# Sheet_1.net
KiCad netlist of a schematic drawn in Altium Designer
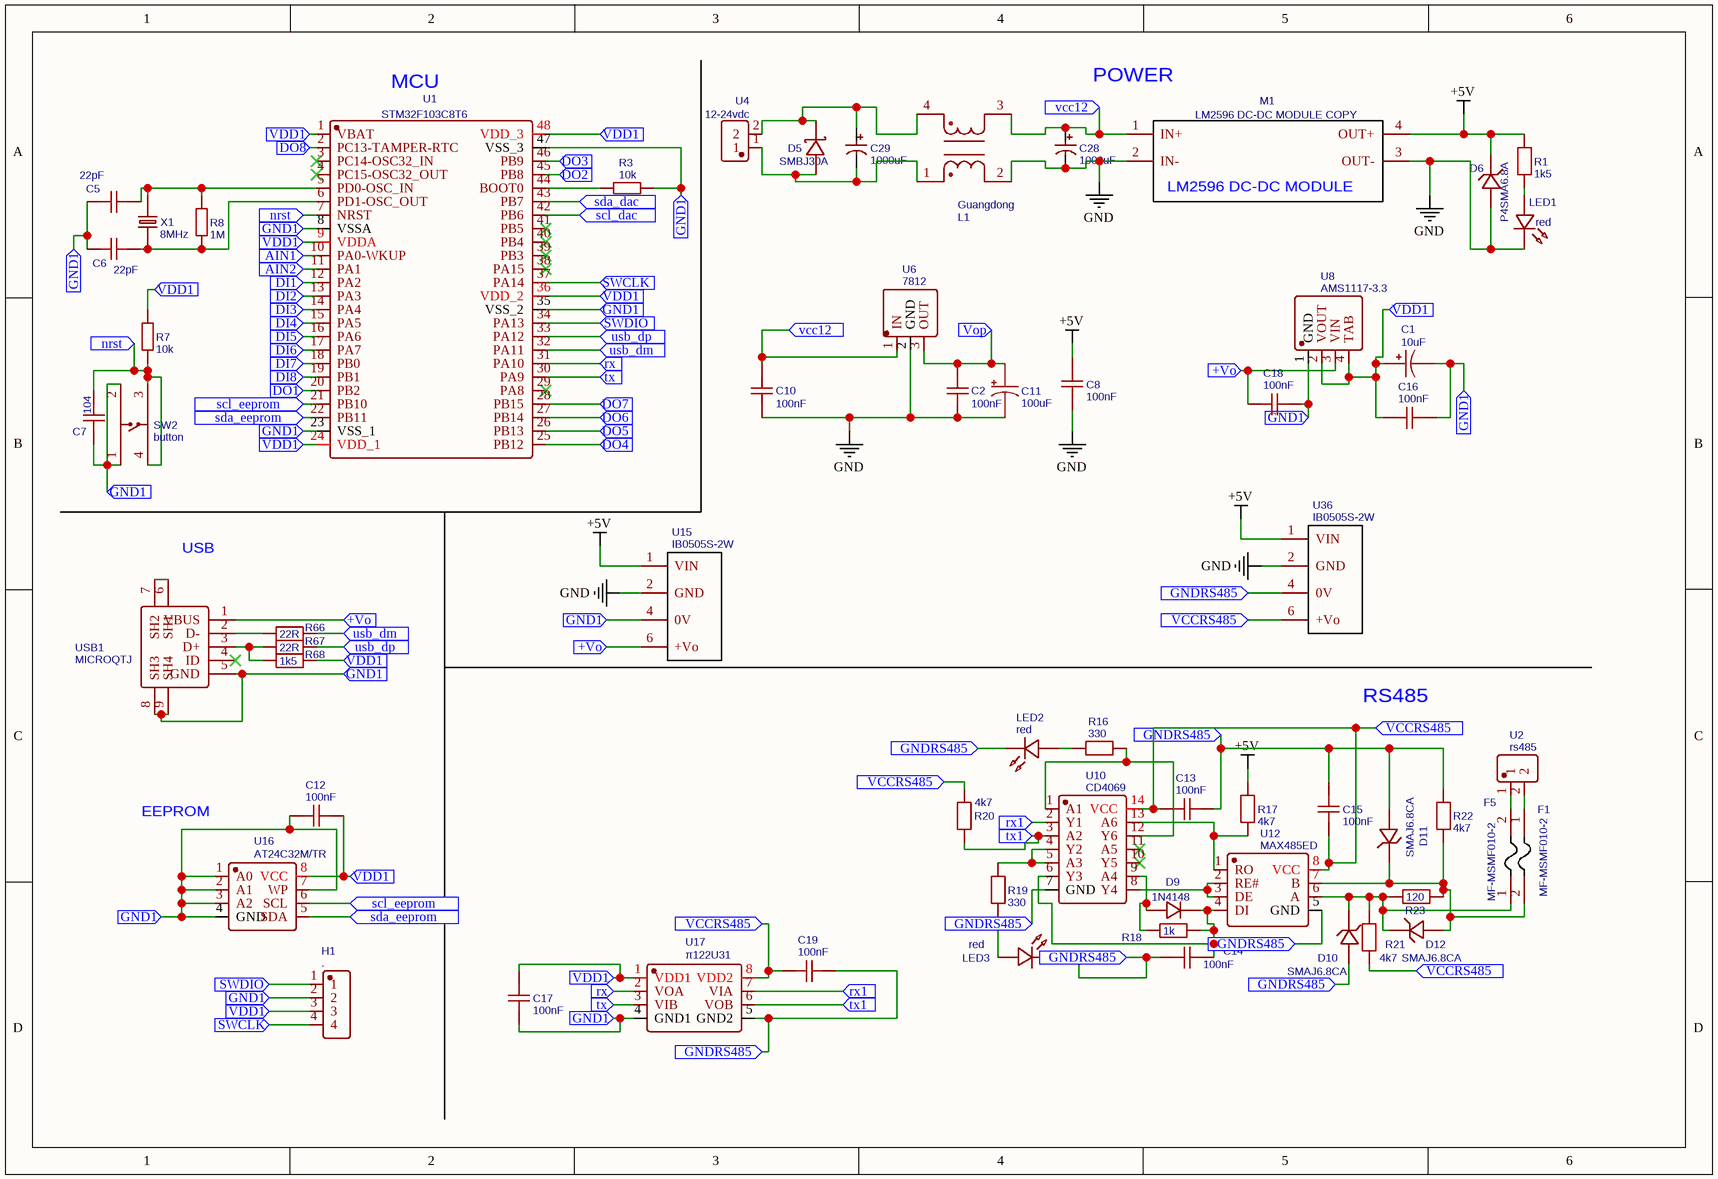
[diagram p0: Sheet_1.schdoc]

(export (version "E")
  (design (tool "Eeschema 10.0.6"))
  (components
    (comp (ref "C1")
      (value "10uF")
      (fields
        (field (name "BOM_SUPPLIER PART") "C503219")
        (field (name "BOM_MANUFACTURER PART") "01EC1809SHC10UF50V")
        (field (name "CONTRIBUTOR") "LCSC")
      )
      (libsource (lib "altium-import") (part "root_0_10uF_"))
    )
    (comp (ref "C2")
      (value "100nF")
      (fields
        (field (name "BOM_SUPPLIER PART") "C254075")
        (field (name "BOM_MANUFACTURER PART") "CC1H333ZA1PD3F4D30MF")
        (field (name "CONTRIBUTOR") "LCSC")
      )
      (libsource (lib "altium-import") (part "root_0_100nF_"))
    )
    (comp (ref "C5")
      (value "22pF")
      (fields
        (field (name "BOM_SUPPLIER PART") "C277970")
        (field (name "BOM_MANUFACTURER PART") "CC1-F5U2J2B330KSPW")
        (field (name "CONTRIBUTOR") "LCSC")
      )
      (libsource (lib "altium-import") (part "root_0_22pF_"))
    )
    (comp (ref "C6")
      (value "22pF")
      (fields
        (field (name "BOM_SUPPLIER PART") "C277970")
        (field (name "BOM_MANUFACTURER PART") "CC1-F5U2J2B330KSPW")
        (field (name "CONTRIBUTOR") "LCSC")
      )
      (libsource (lib "altium-import") (part "root_0_22pF_"))
    )
    (comp (ref "C7")
      (value "104")
      (fields
        (field (name "BOM_SUPPLIER PART") "C277970")
        (field (name "BOM_MANUFACTURER PART") "CC1-F5U2J2B330KSPW")
        (field (name "CONTRIBUTOR") "LCSC")
      )
      (libsource (lib "altium-import") (part "root_1_104_"))
    )
    (comp (ref "C8")
      (value "100nF")
      (fields
        (field (name "BOM_SUPPLIER PART") "C254075")
        (field (name "BOM_MANUFACTURER PART") "CC1H333ZA1PD3F4D30MF")
        (field (name "CONTRIBUTOR") "LCSC")
      )
      (libsource (lib "altium-import") (part "root_2_100nF_"))
    )
    (comp (ref "C10")
      (value "100nF")
      (fields
        (field (name "BOM_SUPPLIER PART") "C254075")
        (field (name "BOM_MANUFACTURER PART") "CC1H333ZA1PD3F4D30MF")
        (field (name "CONTRIBUTOR") "LCSC")
      )
      (libsource (lib "altium-import") (part "root_0_100nF_"))
    )
    (comp (ref "C11")
      (value "100uF")
      (fields
        (field (name "BOM_SUPPLIER PART") "C503221")
        (field (name "BOM_MANUFACTURER PART") "01EC1227SHC470UF25V")
        (field (name "CONTRIBUTOR") "LCSC")
      )
      (libsource (lib "altium-import") (part "root_0_100uF_"))
    )
    (comp (ref "C12")
      (value "100nF")
      (fields
        (field (name "BOM_SUPPLIER PART") "C254075")
        (field (name "BOM_MANUFACTURER PART") "CC1H333ZA1PD3F4D30MF")
        (field (name "CONTRIBUTOR") "LCSC")
      )
      (libsource (lib "altium-import") (part "root_1_100nF_"))
    )
    (comp (ref "C13")
      (value "100nF")
      (fields
        (field (name "BOM_SUPPLIER PART") "C254075")
        (field (name "BOM_MANUFACTURER PART") "CC1H333ZA1PD3F4D30MF")
        (field (name "CONTRIBUTOR") "LCSC")
      )
      (libsource (lib "altium-import") (part "root_1_100nF_"))
    )
    (comp (ref "C14")
      (value "100nF")
      (fields
        (field (name "BOM_SUPPLIER PART") "C254075")
        (field (name "BOM_MANUFACTURER PART") "CC1H333ZA1PD3F4D30MF")
        (field (name "CONTRIBUTOR") "LCSC")
      )
      (libsource (lib "altium-import") (part "root_3_100nF_"))
    )
    (comp (ref "C15")
      (value "100nF")
      (fields
        (field (name "BOM_SUPPLIER PART") "C254075")
        (field (name "BOM_MANUFACTURER PART") "CC1H333ZA1PD3F4D30MF")
        (field (name "CONTRIBUTOR") "LCSC")
      )
      (libsource (lib "altium-import") (part "root_2_100nF_"))
    )
    (comp (ref "C16")
      (value "100nF")
      (fields
        (field (name "BOM_SUPPLIER PART") "C254075")
        (field (name "BOM_MANUFACTURER PART") "CC1H333ZA1PD3F4D30MF")
        (field (name "CONTRIBUTOR") "LCSC")
      )
      (libsource (lib "altium-import") (part "root_1_100nF_"))
    )
    (comp (ref "C17")
      (value "100nF")
      (fields
        (field (name "BOM_SUPPLIER PART") "C254075")
        (field (name "BOM_MANUFACTURER PART") "CC1H333ZA1PD3F4D30MF")
        (field (name "CONTRIBUTOR") "LCSC")
      )
      (libsource (lib "altium-import") (part "root_2_100nF_"))
    )
    (comp (ref "C18")
      (value "100nF")
      (fields
        (field (name "BOM_SUPPLIER PART") "C254075")
        (field (name "BOM_MANUFACTURER PART") "CC1H333ZA1PD3F4D30MF")
        (field (name "CONTRIBUTOR") "LCSC")
      )
      (libsource (lib "altium-import") (part "root_1_100nF_"))
    )
    (comp (ref "C19")
      (value "100nF")
      (fields
        (field (name "BOM_SUPPLIER PART") "C254075")
        (field (name "BOM_MANUFACTURER PART") "CC1H333ZA1PD3F4D30MF")
        (field (name "CONTRIBUTOR") "LCSC")
      )
      (libsource (lib "altium-import") (part "root_1_100nF_"))
    )
    (comp (ref "C28")
      (value "1000uF")
      (fields
        (field (name "BOM_MANUFACTURER PART") "1000uF 35V 13*20")
        (field (name "BOM_SUPPLIER PART") "C10749")
      )
      (libsource (lib "altium-import") (part "root_3_1000uF_"))
    )
    (comp (ref "C29")
      (value "1000uF")
      (fields
        (field (name "BOM_MANUFACTURER PART") "1000uF 35V 13*20")
        (field (name "BOM_SUPPLIER PART") "C10749")
      )
      (libsource (lib "altium-import") (part "root_3_1000uF_"))
    )
    (comp (ref "D5")
      (value "SMBJ30A")
      (fields (field (name "BOM_SUPPLIER PART") "C305669") (field (name "CONTRIBUTOR") "LCSC"))
      (libsource (lib "altium-import") (part "root_3_SMBJ30A_"))
    )
    (comp (ref "D6")
      (value "P4SMA6.8A")
      (fields (field (name "BOM_SUPPLIER PART") "C2758558") (field (name "CONTRIBUTOR") "LCSC"))
      (libsource (lib "altium-import") (part "root_3_P4SMA6.8A_"))
    )
    (comp (ref "D9")
      (value "1N4148")
      (fields (field (name "BOM_SUPPLIER PART") "C85057"))
      (libsource (lib "altium-import") (part "root_2_1N4148_"))
    )
    (comp (ref "D10")
      (value "SMAJ6.8CA")
      (fields
        (field (name "BOM_SUPPLIER PART") "C521797")
        (field (name "BOM_MANUFACTURER PART") "1.5KE12A")
        (field (name "CONTRIBUTOR") "LCSC")
      )
      (libsource (lib "altium-import") (part "root_3_SMAJ6.8CA_"))
    )
    (comp (ref "D11")
      (value "SMAJ6.8CA")
      (fields
        (field (name "BOM_SUPPLIER PART") "C521797")
        (field (name "BOM_MANUFACTURER PART") "1.5KE12A")
        (field (name "CONTRIBUTOR") "LCSC")
      )
      (libsource (lib "altium-import") (part "root_1_SMAJ6.8CA_"))
    )
    (comp (ref "D12")
      (value "SMAJ6.8CA")
      (fields
        (field (name "BOM_SUPPLIER PART") "C521797")
        (field (name "BOM_MANUFACTURER PART") "1.5KE12A")
        (field (name "CONTRIBUTOR") "LCSC")
      )
      (libsource (lib "altium-import") (part "root_0_SMAJ6.8CA_"))
    )
    (comp (ref "F1")
      (value "MF-MSMF010-2")
      (fields (field (name "BOM_SUPPLIER PART") "C12430"))
      (libsource (lib "altium-import") (part "root_3_MF-MSMF010-2_"))
    )
    (comp (ref "F5")
      (value "MF-MSMF010-2")
      (fields (field (name "BOM_SUPPLIER PART") "C12430"))
      (libsource (lib "altium-import") (part "root_1_MF-MSMF010-2_"))
    )
    (comp (ref "H1")
      (value ".")
      (fields
        (field (name "BOM_SUPPLIER PART") "C355292")
        (field (name "BOM_MANUFACTURER PART") "12251104CNSNS295001")
        (field (name "CONTRIBUTOR") "LCSC")
      )
      (libsource (lib "altium-import") (part "root_0_._"))
    )
    (comp (ref "L1")
      (value "Guangdong")
      (fields
        (field (name "BOM_SUPPLIER PART") "C116373")
        (field (name "BOM_MANUFACTURER PART") "UU9.8-5mH")
        (field (name "CONTRIBUTOR") "LCSC")
      )
      (libsource (lib "altium-import") (part "root_0_Guangdong_"))
    )
    (comp (ref "LED1")
      (value "red")
      (fields
        (field (name "BOM_SUPPLIER PART") "C568941")
        (field (name "BOM_MANUFACTURER PART") "HL-503H3GD")
        (field (name "CONTRIBUTOR") "LCSC")
      )
      (libsource (lib "altium-import") (part "root_3_red_"))
    )
    (comp (ref "LED2")
      (value "red")
      (fields
        (field (name "BOM_SUPPLIER PART") "C568941")
        (field (name "BOM_MANUFACTURER PART") "HL-503H3GD")
        (field (name "CONTRIBUTOR") "LCSC")
      )
      (libsource (lib "altium-import") (part "root_2_red_"))
    )
    (comp (ref "LED3")
      (value "red")
      (fields
        (field (name "BOM_SUPPLIER PART") "C568941")
        (field (name "BOM_MANUFACTURER PART") "HL-503H3GD")
        (field (name "CONTRIBUTOR") "LCSC")
      )
      (libsource (lib "altium-import") (part "root_0_red_"))
    )
    (comp (ref "M1")
      (value "LM2596 DC-DC MODULE COPY")
      (fields
        (field (name "BOM_MANUFACTURER PART") "New SchematicLib")
        (field (name "CONTRIBUTOR") "erikkate")
      )
      (libsource (lib "altium-import") (part "root_0_LM2596 DC-DC MODULE COPY_"))
    )
    (comp (ref "R1")
      (value "1k5")
      (fields
        (field (name "BOM_SUPPLIER PART") "C410678")
        (field (name "BOM_MANUFACTURER PART") "RN 1/4W 1K5 F T/B A1")
        (field (name "CONTRIBUTOR") "LCSC")
      )
      (libsource (lib "altium-import") (part "root_1_1k5_"))
    )
    (comp (ref "R3")
      (value "10k")
      (fields (field (name "BOM_SUPPLIER PART") "C120038") (field (name "CONTRIBUTOR") "LCSC"))
      (libsource (lib "altium-import") (part "root_0_10k_"))
    )
    (comp (ref "R7")
      (value "10k")
      (fields (field (name "BOM_SUPPLIER PART") "C120038") (field (name "CONTRIBUTOR") "LCSC"))
      (libsource (lib "altium-import") (part "root_1_10k_"))
    )
    (comp (ref "R8")
      (value "1M")
      (fields (field (name "BOM_SUPPLIER PART") "C120038") (field (name "CONTRIBUTOR") "LCSC"))
      (libsource (lib "altium-import") (part "root_1_1M_"))
    )
    (comp (ref "R16")
      (value "330")
      (fields
        (field (name "BOM_SUPPLIER PART") "C410678")
        (field (name "BOM_MANUFACTURER PART") "RN 1/4W 1K5 F T/B A1")
        (field (name "CONTRIBUTOR") "LCSC")
      )
      (libsource (lib "altium-import") (part "root_0_330_"))
    )
    (comp (ref "R17")
      (value "4k7")
      (fields
        (field (name "BOM_SUPPLIER PART") "C410678")
        (field (name "BOM_MANUFACTURER PART") "RN 1/4W 1K5 F T/B A1")
        (field (name "CONTRIBUTOR") "LCSC")
      )
      (libsource (lib "altium-import") (part "root_1_4k7_"))
    )
    (comp (ref "R18")
      (value "1k")
      (fields
        (field (name "BOM_SUPPLIER PART") "C410678")
        (field (name "BOM_MANUFACTURER PART") "RN 1/4W 1K5 F T/B A1")
        (field (name "CONTRIBUTOR") "LCSC")
      )
      (libsource (lib "altium-import") (part "root_2_1k_"))
    )
    (comp (ref "R19")
      (value "330")
      (fields
        (field (name "BOM_SUPPLIER PART") "C410678")
        (field (name "BOM_MANUFACTURER PART") "RN 1/4W 1K5 F T/B A1")
        (field (name "CONTRIBUTOR") "LCSC")
      )
      (libsource (lib "altium-import") (part "root_1_330_"))
    )
    (comp (ref "R20")
      (value "4k7")
      (fields
        (field (name "BOM_SUPPLIER PART") "C410678")
        (field (name "BOM_MANUFACTURER PART") "RN 1/4W 1K5 F T/B A1")
        (field (name "CONTRIBUTOR") "LCSC")
      )
      (libsource (lib "altium-import") (part "root_1_4k7_"))
    )
    (comp (ref "R21")
      (value "4k7")
      (fields
        (field (name "BOM_SUPPLIER PART") "C410678")
        (field (name "BOM_MANUFACTURER PART") "RN 1/4W 1K5 F T/B A1")
        (field (name "CONTRIBUTOR") "LCSC")
      )
      (libsource (lib "altium-import") (part "root_1_4k7_"))
    )
    (comp (ref "R22")
      (value "4k7")
      (fields
        (field (name "BOM_SUPPLIER PART") "C410678")
        (field (name "BOM_MANUFACTURER PART") "RN 1/4W 1K5 F T/B A1")
        (field (name "CONTRIBUTOR") "LCSC")
      )
      (libsource (lib "altium-import") (part "root_1_4k7_"))
    )
    (comp (ref "R23")
      (value "120")
      (fields
        (field (name "BOM_SUPPLIER PART") "C410678")
        (field (name "BOM_MANUFACTURER PART") "RN 1/4W 1K5 F T/B A1")
        (field (name "CONTRIBUTOR") "LCSC")
      )
      (libsource (lib "altium-import") (part "root_2_120_"))
    )
    (comp (ref "R66")
      (value "22R")
      (fields
        (field (name "BOM_SUPPLIER PART") "C410678")
        (field (name "BOM_MANUFACTURER PART") "RN 1/4W 1K5 F T/B A1")
        (field (name "CONTRIBUTOR") "LCSC")
      )
      (libsource (lib "altium-import") (part "root_2_22R_"))
    )
    (comp (ref "R67")
      (value "22R")
      (fields
        (field (name "BOM_SUPPLIER PART") "C410678")
        (field (name "BOM_MANUFACTURER PART") "RN 1/4W 1K5 F T/B A1")
        (field (name "CONTRIBUTOR") "LCSC")
      )
      (libsource (lib "altium-import") (part "root_2_22R_"))
    )
    (comp (ref "R68")
      (value "1k5")
      (fields
        (field (name "BOM_SUPPLIER PART") "C410678")
        (field (name "BOM_MANUFACTURER PART") "RN 1/4W 1K5 F T/B A1")
        (field (name "CONTRIBUTOR") "LCSC")
      )
      (libsource (lib "altium-import") (part "root_2_1k5_"))
    )
    (comp (ref "SW2")
      (value "button")
      (fields
        (field (name "BOM_SUPPLIER PART") "C285482")
        (field (name "BOM_MANUFACTURER PART") "PTS645SL432LFS")
        (field (name "CONTRIBUTOR") "LCSC")
      )
      (libsource (lib "altium-import") (part "root_1_button_"))
    )
    (comp (ref "U1")
      (value "STM32F103C8T6")
      (fields (field (name "BOM_SUPPLIER PART") "C8734"))
      (libsource (lib "altium-import") (part "root_0_STM32F103C8T6_"))
    )
    (comp (ref "U2")
      (value "rs485")
      (fields
        (field (name "BOM_SUPPLIER PART") "C691860")
        (field (name "BOM_MANUFACTURER PART") "DG127-5.08-02P-14-02A(H)")
        (field (name "CONTRIBUTOR") "LCSC")
      )
      (libsource (lib "altium-import") (part "root_1_rs485_"))
    )
    (comp (ref "U4")
      (value "12-24vdc")
      (fields
        (field (name "BOM_SUPPLIER PART") "C691860")
        (field (name "BOM_MANUFACTURER PART") "DG127-5.08-02P-14-02A(H)")
        (field (name "CONTRIBUTOR") "LCSC")
      )
      (libsource (lib "altium-import") (part "root_2_12-24vdc_"))
    )
    (comp (ref "U6")
      (value "7812")
      (fields (field (name "BOM_SUPPLIER PART") "C358369") (field (name "CONTRIBUTOR") "LCSC"))
      (libsource (lib "altium-import") (part "root_1_7812_"))
    )
    (comp (ref "U8")
      (value "AMS1117-3.3")
      (fields (field (name "BOM_SUPPLIER PART") "C498117") (field (name "CONTRIBUTOR") "LCSC"))
      (libsource (lib "altium-import") (part "root_1_AMS1117-3.3_"))
    )
    (comp (ref "U10")
      (value "CD4069")
      (fields
        (field (name "BOM_SUPPLIER PART") "C507186")
        (field (name "BOM_MANUFACTURER PART") "74HC14N")
        (field (name "CONTRIBUTOR") "LCSC")
      )
      (libsource (lib "altium-import") (part "root_0_CD4069_"))
    )
    (comp (ref "U12")
      (value "MAX485ED")
      (fields (field (name "BOM_MANUFACTURER PART") "MAX485EPA+") (field (name "BOM_SUPPLIER PART") "C45829"))
      (libsource (lib "altium-import") (part "root_0_MAX485ED_"))
    )
    (comp (ref "U15")
      (value "IB0505S-2W")
      (fields (field (name "BOM_SUPPLIER PART") "C9758"))
      (libsource (lib "altium-import") (part "root_0_IB0505S-2W_"))
    )
    (comp (ref "U16")
      (value "AT24C32M/TR")
      (fields (field (name "BOM_SUPPLIER PART") "C2688466") (field (name "CONTRIBUTOR") "LCSC"))
      (libsource (lib "altium-import") (part "root_0_AT24C32M/TR_"))
    )
    (comp (ref "U17")
      (value "π122U31")
      (fields (field (name "BOM_SUPPLIER PART") "C471590") (field (name "CONTRIBUTOR") "LCSC"))
      (libsource (lib "altium-import") (part "root_0_π122U31_"))
    )
    (comp (ref "U36")
      (value "IB0505S-2W")
      (fields (field (name "BOM_SUPPLIER PART") "C9758"))
      (libsource (lib "altium-import") (part "root_0_IB0505S-2W_"))
    )
    (comp (ref "USB1")
      (value "MICROQTJ")
      (fields
        (field (name "BOM_SUPPLIER PART") "C404968")
        (field (name "BOM_MANUFACTURER PART") "MicroQTJ")
        (field (name "CONTRIBUTOR") "LCSC")
      )
      (libsource (lib "altium-import") (part "root_0_MICROQTJ_"))
    )
    (comp (ref "X1")
      (value "8MHz")
      (fields
        (field (name "BOM_SUPPLIER PART") "C240941")
        (field (name "BOM_MANUFACTURER PART") "49S-7.6-20-20-20/A")
        (field (name "CONTRIBUTOR") "LCSC")
      )
      (libsource (lib "altium-import") (part "root_1_8MHz_"))
    )
  )
  (nets
    (net (code "1") (name "+5V") (class "Default")
      (node (ref "C8") (pin "1") (pinfunction "1_1") (pintype "passive"))
      (node (ref "D6") (pin "1") (pinfunction "C_1") (pintype "passive"))
      (node (ref "M1") (pin "4") (pinfunction "OUT+_4") (pintype "passive"))
      (node (ref "R1") (pin "2") (pinfunction "2_2") (pintype "passive"))
      (node (ref "R17") (pin "2") (pinfunction "2_2") (pintype "passive"))
      (node (ref "U15") (pin "1") (pinfunction "VIN_1") (pintype "passive"))
      (node (ref "U36") (pin "1") (pinfunction "VIN_1") (pintype "passive"))
    )
    (net (code "2") (name "/+Vo") (class "Default")
      (node (ref "C18") (pin "2") (pinfunction "2_2") (pintype "passive"))
      (node (ref "U15") (pin "6") (pinfunction "+Vo_6") (pintype "passive"))
      (node (ref "U8") (pin "3") (pinfunction "VIN_3") (pintype "passive"))
      (node (ref "USB1") (pin "1") (pinfunction "VBUS_1") (pintype "passive"))
    )
    (net (code "3") (name "/AIN1") (class "Default")
      (node (ref "U1") (pin "10") (pinfunction "PA0-WKUP_10") (pintype "passive"))
    )
    (net (code "4") (name "/AIN2") (class "Default")
      (node (ref "U1") (pin "11") (pinfunction "PA1_11") (pintype "passive"))
    )
    (net (code "5") (name "/DI1") (class "Default")
      (node (ref "U1") (pin "12") (pinfunction "PA2_12") (pintype "passive"))
    )
    (net (code "6") (name "/DI2") (class "Default")
      (node (ref "U1") (pin "13") (pinfunction "PA3_13") (pintype "passive"))
    )
    (net (code "7") (name "/DI3") (class "Default")
      (node (ref "U1") (pin "14") (pinfunction "PA4_14") (pintype "passive"))
    )
    (net (code "8") (name "/DI4") (class "Default")
      (node (ref "U1") (pin "15") (pinfunction "PA5_15") (pintype "passive"))
    )
    (net (code "9") (name "/DI5") (class "Default")
      (node (ref "U1") (pin "16") (pinfunction "PA6_16") (pintype "passive"))
    )
    (net (code "10") (name "/DI6") (class "Default")
      (node (ref "U1") (pin "17") (pinfunction "PA7_17") (pintype "passive"))
    )
    (net (code "11") (name "/DI7") (class "Default")
      (node (ref "U1") (pin "18") (pinfunction "PB0_18") (pintype "passive"))
    )
    (net (code "12") (name "/DI8") (class "Default")
      (node (ref "U1") (pin "19") (pinfunction "PB1_19") (pintype "passive"))
    )
    (net (code "13") (name "/DO1") (class "Default")
      (node (ref "U1") (pin "20") (pinfunction "PB2_20") (pintype "passive"))
    )
    (net (code "14") (name "/DO2") (class "Default")
      (node (ref "U1") (pin "45") (pinfunction "PB8_45") (pintype "passive"))
    )
    (net (code "15") (name "/DO3") (class "Default")
      (node (ref "U1") (pin "46") (pinfunction "PB9_46") (pintype "passive"))
    )
    (net (code "16") (name "/DO4") (class "Default")
      (node (ref "U1") (pin "25") (pinfunction "PB12_25") (pintype "passive"))
    )
    (net (code "17") (name "/DO5") (class "Default")
      (node (ref "U1") (pin "26") (pinfunction "PB13_26") (pintype "passive"))
    )
    (net (code "18") (name "/DO6") (class "Default")
      (node (ref "U1") (pin "27") (pinfunction "PB14_27") (pintype "passive"))
    )
    (net (code "19") (name "/DO7") (class "Default")
      (node (ref "U1") (pin "28") (pinfunction "PB15_28") (pintype "passive"))
    )
    (net (code "20") (name "/DO8") (class "Default")
      (node (ref "U1") (pin "2") (pinfunction "PC13-TAMPER-RTC_2") (pintype "passive"))
    )
    (net (code "21") (name "/GND1") (class "Default")
      (node (ref "C1") (pin "2") (pinfunction "2_2") (pintype "passive"))
      (node (ref "C12") (pin "2") (pinfunction "2_2") (pintype "passive"))
      (node (ref "C16") (pin "1") (pinfunction "1_1") (pintype "passive"))
      (node (ref "C17") (pin "2") (pinfunction "2_2") (pintype "passive"))
      (node (ref "C18") (pin "1") (pinfunction "1_1") (pintype "passive"))
      (node (ref "C5") (pin "1") (pinfunction "1_1") (pintype "passive"))
      (node (ref "C6") (pin "1") (pinfunction "1_1") (pintype "passive"))
      (node (ref "C7") (pin "1") (pinfunction "1_1") (pintype "passive"))
      (node (ref "H1") (pin "2") (pinfunction "2_2") (pintype "passive"))
      (node (ref "R3") (pin "2") (pinfunction "2_2") (pintype "passive"))
      (node (ref "SW2") (pin "1") (pinfunction "1_1") (pintype "passive"))
      (node (ref "SW2") (pin "2") (pinfunction "2_2") (pintype "passive"))
      (node (ref "U1") (pin "23") (pinfunction "VSS_1_23") (pintype "passive"))
      (node (ref "U1") (pin "35") (pinfunction "VSS_2_35") (pintype "passive"))
      (node (ref "U1") (pin "47") (pinfunction "VSS_3_47") (pintype "passive"))
      (node (ref "U1") (pin "8") (pinfunction "VSSA_8") (pintype "passive"))
      (node (ref "U15") (pin "4") (pinfunction "0V_4") (pintype "passive"))
      (node (ref "U16") (pin "1") (pinfunction "A0_1") (pintype "passive"))
      (node (ref "U16") (pin "2") (pinfunction "A1_2") (pintype "passive"))
      (node (ref "U16") (pin "3") (pinfunction "A2_3") (pintype "passive"))
      (node (ref "U16") (pin "4") (pinfunction "GND_4") (pintype "passive"))
      (node (ref "U16") (pin "7") (pinfunction "WP_7") (pintype "passive"))
      (node (ref "U17") (pin "4") (pinfunction "GND1_4") (pintype "passive"))
      (node (ref "U8") (pin "1") (pinfunction "GND_1") (pintype "passive"))
      (node (ref "USB1") (pin "5") (pinfunction "GND_5") (pintype "passive"))
      (node (ref "USB1") (pin "8") (pinfunction "SH3_8") (pintype "passive"))
      (node (ref "USB1") (pin "9") (pinfunction "SH4_9") (pintype "passive"))
    )
    (net (code "22") (name "/GNDRS485") (class "Default")
      (node (ref "C13") (pin "1") (pinfunction "1_1") (pintype "passive"))
      (node (ref "C14") (pin "1") (pinfunction "1_1") (pintype "passive"))
      (node (ref "C14") (pin "2") (pinfunction "2_2") (pintype "passive"))
      (node (ref "C15") (pin "1") (pinfunction "1_1") (pintype "passive"))
      (node (ref "C19") (pin "1") (pinfunction "1_1") (pintype "passive"))
      (node (ref "D10") (pin "2") (pinfunction "A_2") (pintype "passive"))
      (node (ref "D11") (pin "2") (pinfunction "A_2") (pintype "passive"))
      (node (ref "D9") (pin "1") (pinfunction "C_1") (pintype "passive"))
      (node (ref "LED2") (pin "2") (pinfunction "2_2") (pintype "passive"))
      (node (ref "LED3") (pin "2") (pinfunction "2_2") (pintype "passive"))
      (node (ref "R18") (pin "1") (pinfunction "1_1") (pintype "passive"))
      (node (ref "R22") (pin "2") (pinfunction "2_2") (pintype "passive"))
      (node (ref "U10") (pin "6") (pinfunction "Y3_6") (pintype "passive"))
      (node (ref "U10") (pin "7") (pinfunction "GND_7") (pintype "passive"))
      (node (ref "U12") (pin "4") (pinfunction "DI_4") (pintype "passive"))
      (node (ref "U12") (pin "5") (pinfunction "GND_5") (pintype "passive"))
      (node (ref "U17") (pin "5") (pinfunction "GND2_5") (pintype "passive"))
      (node (ref "U36") (pin "4") (pinfunction "0V_4") (pintype "passive"))
    )
    (net (code "23") (name "/SWCLK") (class "Default")
      (node (ref "H1") (pin "4") (pinfunction "4_4") (pintype "passive"))
      (node (ref "U1") (pin "37") (pinfunction "PA14_37") (pintype "passive"))
    )
    (net (code "24") (name "/SWDIO") (class "Default")
      (node (ref "H1") (pin "1") (pinfunction "1_1") (pintype "passive"))
      (node (ref "U1") (pin "34") (pinfunction "PA13_34") (pintype "passive"))
    )
    (net (code "25") (name "/VCCRS485") (class "Default")
      (node (ref "C13") (pin "2") (pinfunction "2_2") (pintype "passive"))
      (node (ref "C15") (pin "2") (pinfunction "2_2") (pintype "passive"))
      (node (ref "C19") (pin "2") (pinfunction "2_2") (pintype "passive"))
      (node (ref "R20") (pin "2") (pinfunction "2_2") (pintype "passive"))
      (node (ref "R21") (pin "1") (pinfunction "1_1") (pintype "passive"))
      (node (ref "U10") (pin "14") (pinfunction "VCC_14") (pintype "passive"))
      (node (ref "U12") (pin "8") (pinfunction "VCC_8") (pintype "passive"))
      (node (ref "U17") (pin "8") (pinfunction "VDD2_8") (pintype "passive"))
      (node (ref "U36") (pin "6") (pinfunction "+Vo_6") (pintype "passive"))
    )
    (net (code "26") (name "/VDD1") (class "Default")
      (node (ref "C1") (pin "1") (pinfunction "1_1") (pintype "passive"))
      (node (ref "C12") (pin "1") (pinfunction "1_1") (pintype "passive"))
      (node (ref "C16") (pin "2") (pinfunction "2_2") (pintype "passive"))
      (node (ref "C17") (pin "1") (pinfunction "1_1") (pintype "passive"))
      (node (ref "H1") (pin "3") (pinfunction "3_3") (pintype "passive"))
      (node (ref "R68") (pin "1") (pinfunction "1_1") (pintype "passive"))
      (node (ref "R7") (pin "2") (pinfunction "2_2") (pintype "passive"))
      (node (ref "U1") (pin "1") (pinfunction "VBAT_1") (pintype "passive"))
      (node (ref "U1") (pin "24") (pinfunction "VDD_1_24") (pintype "passive"))
      (node (ref "U1") (pin "36") (pinfunction "VDD_2_36") (pintype "passive"))
      (node (ref "U1") (pin "48") (pinfunction "VDD_3_48") (pintype "passive"))
      (node (ref "U1") (pin "9") (pinfunction "VDDA_9") (pintype "passive"))
      (node (ref "U16") (pin "8") (pinfunction "VCC_8") (pintype "passive"))
      (node (ref "U17") (pin "1") (pinfunction "VDD1_1") (pintype "passive"))
      (node (ref "U8") (pin "2") (pinfunction "VOUT_2") (pintype "passive"))
      (node (ref "U8") (pin "4") (pinfunction "TAB_4") (pintype "passive"))
    )
    (net (code "27") (name "/Vop") (class "Default")
      (node (ref "C11") (pin "1") (pinfunction "1_1") (pintype "passive"))
      (node (ref "C2") (pin "2") (pinfunction "2_2") (pintype "passive"))
      (node (ref "U6") (pin "3") (pinfunction "OUT_3") (pintype "passive"))
    )
    (net (code "28") (name "/nrst") (class "Default")
      (node (ref "C7") (pin "2") (pinfunction "2_2") (pintype "passive"))
      (node (ref "R7") (pin "1") (pinfunction "1_1") (pintype "passive"))
      (node (ref "SW2") (pin "3") (pinfunction "3_3") (pintype "passive"))
      (node (ref "SW2") (pin "4") (pinfunction "4_4") (pintype "passive"))
      (node (ref "U1") (pin "7") (pinfunction "NRST_7") (pintype "passive"))
    )
    (net (code "29") (name "/rx") (class "Default")
      (node (ref "U1") (pin "31") (pinfunction "PA10_31") (pintype "passive"))
      (node (ref "U17") (pin "2") (pinfunction "VOA_2") (pintype "passive"))
    )
    (net (code "30") (name "/rx1") (class "Default")
      (node (ref "U10") (pin "2") (pinfunction "Y1_2") (pintype "passive"))
      (node (ref "U17") (pin "7") (pinfunction "VIA_7") (pintype "passive"))
    )
    (net (code "31") (name "/scl_dac") (class "Default")
      (node (ref "U1") (pin "42") (pinfunction "PB6_42") (pintype "passive"))
    )
    (net (code "32") (name "/scl_eeprom") (class "Default")
      (node (ref "U1") (pin "21") (pinfunction "PB10_21") (pintype "passive"))
      (node (ref "U16") (pin "6") (pinfunction "SCL_6") (pintype "passive"))
    )
    (net (code "33") (name "/sda_dac") (class "Default")
      (node (ref "U1") (pin "43") (pinfunction "PB7_43") (pintype "passive"))
    )
    (net (code "34") (name "/sda_eeprom") (class "Default")
      (node (ref "U1") (pin "22") (pinfunction "PB11_22") (pintype "passive"))
      (node (ref "U16") (pin "5") (pinfunction "SDA_5") (pintype "passive"))
    )
    (net (code "35") (name "/tx") (class "Default")
      (node (ref "U1") (pin "30") (pinfunction "PA9_30") (pintype "passive"))
      (node (ref "U17") (pin "3") (pinfunction "VIB_3") (pintype "passive"))
    )
    (net (code "36") (name "/tx1") (class "Default")
      (node (ref "R20") (pin "1") (pinfunction "1_1") (pintype "passive"))
      (node (ref "U10") (pin "3") (pinfunction "A2_3") (pintype "passive"))
      (node (ref "U17") (pin "6") (pinfunction "VOB_6") (pintype "passive"))
    )
    (net (code "37") (name "/usb_dm") (class "Default")
      (node (ref "R66") (pin "1") (pinfunction "1_1") (pintype "passive"))
      (node (ref "U1") (pin "32") (pinfunction "PA11_32") (pintype "passive"))
    )
    (net (code "38") (name "/usb_dp") (class "Default")
      (node (ref "R67") (pin "1") (pinfunction "1_1") (pintype "passive"))
      (node (ref "U1") (pin "33") (pinfunction "PA12_33") (pintype "passive"))
    )
    (net (code "39") (name "/vcc12") (class "Default")
      (node (ref "C10") (pin "2") (pinfunction "2_2") (pintype "passive"))
      (node (ref "C28") (pin "1") (pinfunction "1_1") (pintype "passive"))
      (node (ref "L1") (pin "3") (pinfunction "3_3") (pintype "passive"))
      (node (ref "M1") (pin "1") (pinfunction "IN+_1") (pintype "passive"))
      (node (ref "U6") (pin "1") (pinfunction "IN_1") (pintype "passive"))
    )
    (net (code "40") (name "GND") (class "Default")
      (node (ref "C10") (pin "1") (pinfunction "1_1") (pintype "passive"))
      (node (ref "C11") (pin "2") (pinfunction "2_2") (pintype "passive"))
      (node (ref "C2") (pin "1") (pinfunction "1_1") (pintype "passive"))
      (node (ref "C28") (pin "2") (pinfunction "2_2") (pintype "passive"))
      (node (ref "C8") (pin "2") (pinfunction "2_2") (pintype "passive"))
      (node (ref "D6") (pin "2") (pinfunction "A_2") (pintype "passive"))
      (node (ref "L1") (pin "2") (pinfunction "2_2") (pintype "passive"))
      (node (ref "LED1") (pin "2") (pinfunction "2_2") (pintype "passive"))
      (node (ref "M1") (pin "2") (pinfunction "IN-_2") (pintype "passive"))
      (node (ref "M1") (pin "3") (pinfunction "OUT-_3") (pintype "passive"))
      (node (ref "U15") (pin "2") (pinfunction "GND_2") (pintype "passive"))
      (node (ref "U36") (pin "2") (pinfunction "GND_2") (pintype "passive"))
      (node (ref "U6") (pin "2") (pinfunction "GND_2") (pintype "passive"))
    )
    (net (code "41") (name "Net-(D5-A)") (class "Default")
      (node (ref "C29") (pin "2") (pinfunction "2_2") (pintype "passive"))
      (node (ref "D5") (pin "1") (pinfunction "A_1") (pintype "passive"))
      (node (ref "L1") (pin "1") (pinfunction "1_1") (pintype "passive"))
      (node (ref "U4") (pin "1") (pinfunction "1_1") (pintype "passive"))
    )
    (net (code "42") (name "Net-(D5-K)") (class "Default")
      (node (ref "C29") (pin "1") (pinfunction "1_1") (pintype "passive"))
      (node (ref "D5") (pin "2") (pinfunction "K_2") (pintype "passive"))
      (node (ref "L1") (pin "4") (pinfunction "4_4") (pintype "passive"))
      (node (ref "U4") (pin "2") (pinfunction "2_2") (pintype "passive"))
    )
    (net (code "43") (name "Net-(D9-A)") (class "Default")
      (node (ref "D9") (pin "2") (pinfunction "A_2") (pintype "passive"))
      (node (ref "R18") (pin "2") (pinfunction "2_2") (pintype "passive"))
      (node (ref "U10") (pin "9") (pinfunction "A4_9") (pintype "passive"))
    )
    (net (code "44") (name "Net-(D10-C)") (class "Default")
      (node (ref "D10") (pin "1") (pinfunction "C_1") (pintype "passive"))
      (node (ref "D12") (pin "1") (pinfunction "C_1") (pintype "passive"))
      (node (ref "F5") (pin "1") (pinfunction "1_1") (pintype "passive"))
      (node (ref "R21") (pin "2") (pinfunction "2_2") (pintype "passive"))
      (node (ref "R23") (pin "2") (pinfunction "2_2") (pintype "passive"))
      (node (ref "U12") (pin "6") (pinfunction "A_6") (pintype "passive"))
    )
    (net (code "45") (name "Net-(D11-C)") (class "Default")
      (node (ref "D11") (pin "1") (pinfunction "C_1") (pintype "passive"))
      (node (ref "D12") (pin "2") (pinfunction "A_2") (pintype "passive"))
      (node (ref "F1") (pin "2") (pinfunction "2_2") (pintype "passive"))
      (node (ref "R22") (pin "1") (pinfunction "1_1") (pintype "passive"))
      (node (ref "R23") (pin "1") (pinfunction "1_1") (pintype "passive"))
      (node (ref "U12") (pin "7") (pinfunction "B_7") (pintype "passive"))
    )
    (net (code "46") (name "Net-(F1-Pad1)") (class "Default")
      (node (ref "F1") (pin "1") (pinfunction "1_1") (pintype "passive"))
      (node (ref "U2") (pin "2") (pinfunction "2_2") (pintype "passive"))
    )
    (net (code "47") (name "Net-(F5-Pad2)") (class "Default")
      (node (ref "F5") (pin "2") (pinfunction "2_2") (pintype "passive"))
      (node (ref "U2") (pin "1") (pinfunction "1_1") (pintype "passive"))
    )
    (net (code "48") (name "Net-(LED1-Pad1)") (class "Default")
      (node (ref "LED1") (pin "1") (pinfunction "1_1") (pintype "passive"))
      (node (ref "R1") (pin "1") (pinfunction "1_1") (pintype "passive"))
    )
    (net (code "49") (name "Net-(LED2-Pad1)") (class "Default")
      (node (ref "LED2") (pin "1") (pinfunction "1_1") (pintype "passive"))
      (node (ref "R16") (pin "1") (pinfunction "1_1") (pintype "passive"))
    )
    (net (code "50") (name "Net-(LED3-Pad1)") (class "Default")
      (node (ref "LED3") (pin "1") (pinfunction "1_1") (pintype "passive"))
      (node (ref "R19") (pin "1") (pinfunction "1_1") (pintype "passive"))
    )
    (net (code "51") (name "Net-(U1-BOOT0)") (class "Default")
      (node (ref "R3") (pin "1") (pinfunction "1_1") (pintype "passive"))
      (node (ref "U1") (pin "44") (pinfunction "BOOT0_44") (pintype "passive"))
    )
    (net (code "52") (name "Net-(U1-PD0-OSC_IN)") (class "Default")
      (node (ref "C5") (pin "2") (pinfunction "2_2") (pintype "passive"))
      (node (ref "R8") (pin "2") (pinfunction "2_2") (pintype "passive"))
      (node (ref "U1") (pin "5") (pinfunction "PD0-OSC_IN_5") (pintype "passive"))
      (node (ref "X1") (pin "2") (pinfunction "2_2") (pintype "passive"))
    )
    (net (code "53") (name "Net-(U1-PD1-OSC_OUT)") (class "Default")
      (node (ref "C6") (pin "2") (pinfunction "2_2") (pintype "passive"))
      (node (ref "R8") (pin "1") (pinfunction "1_1") (pintype "passive"))
      (node (ref "U1") (pin "6") (pinfunction "PD1-OSC_OUT_6") (pintype "passive"))
      (node (ref "X1") (pin "1") (pinfunction "1_1") (pintype "passive"))
    )
    (net (code "54") (name "Net-(U10-A1)") (class "Default")
      (node (ref "R16") (pin "2") (pinfunction "2_2") (pintype "passive"))
      (node (ref "U10") (pin "1") (pinfunction "A1_1") (pintype "passive"))
      (node (ref "U10") (pin "12") (pinfunction "Y6_12") (pintype "passive"))
    )
    (net (code "55") (name "Net-(U10-A3)") (class "Default")
      (node (ref "R19") (pin "2") (pinfunction "2_2") (pintype "passive"))
      (node (ref "U10") (pin "4") (pinfunction "Y2_4") (pintype "passive"))
      (node (ref "U10") (pin "5") (pinfunction "A3_5") (pintype "passive"))
    )
    (net (code "56") (name "Net-(U10-A6)") (class "Default")
      (node (ref "R17") (pin "1") (pinfunction "1_1") (pintype "passive"))
      (node (ref "U10") (pin "13") (pinfunction "A6_13") (pintype "passive"))
      (node (ref "U12") (pin "1") (pinfunction "RO_1") (pintype "passive"))
    )
    (net (code "57") (name "Net-(U10-Y4)") (class "Default")
      (node (ref "U10") (pin "8") (pinfunction "Y4_8") (pintype "passive"))
      (node (ref "U12") (pin "2") (pinfunction "RE#_2") (pintype "passive"))
      (node (ref "U12") (pin "3") (pinfunction "DE_3") (pintype "passive"))
    )
    (net (code "58") (name "Net-(USB1-D+)") (class "Default")
      (node (ref "R67") (pin "2") (pinfunction "2_2") (pintype "passive"))
      (node (ref "R68") (pin "2") (pinfunction "2_2") (pintype "passive"))
      (node (ref "USB1") (pin "3") (pinfunction "D+_3") (pintype "passive"))
    )
    (net (code "59") (name "Net-(USB1-D-)") (class "Default")
      (node (ref "R66") (pin "2") (pinfunction "2_2") (pintype "passive"))
      (node (ref "USB1") (pin "2") (pinfunction "D-_2") (pintype "passive"))
    )
    (net (code "60") (name "Net-(USB1-SH1)") (class "Default")
      (node (ref "USB1") (pin "6") (pinfunction "SH1_6") (pintype "passive"))
      (node (ref "USB1") (pin "7") (pinfunction "SH2_7") (pintype "passive"))
    )
    (net (code "61") (name "unconnected-(U1-PA8-Pad29)") (class "Default")
      (node (ref "U1") (pin "29") (pinfunction "PA8_29") (pintype "passive+no_connect"))
    )
    (net (code "62") (name "unconnected-(U1-PA15-Pad38)") (class "Default")
      (node (ref "U1") (pin "38") (pinfunction "PA15_38") (pintype "passive+no_connect"))
    )
    (net (code "63") (name "unconnected-(U1-PB3-Pad39)") (class "Default")
      (node (ref "U1") (pin "39") (pinfunction "PB3_39") (pintype "passive+no_connect"))
    )
    (net (code "64") (name "unconnected-(U1-PB4-Pad40)") (class "Default")
      (node (ref "U1") (pin "40") (pinfunction "PB4_40") (pintype "passive+no_connect"))
    )
    (net (code "65") (name "unconnected-(U1-PB5-Pad41)") (class "Default")
      (node (ref "U1") (pin "41") (pinfunction "PB5_41") (pintype "passive+no_connect"))
    )
    (net (code "66") (name "unconnected-(U1-PC14-OSC32_IN-Pad3)") (class "Default")
      (node (ref "U1") (pin "3") (pinfunction "PC14-OSC32_IN_3") (pintype "passive+no_connect"))
    )
    (net (code "67") (name "unconnected-(U1-PC15-OSC32_OUT-Pad4)") (class "Default")
      (node (ref "U1") (pin "4") (pinfunction "PC15-OSC32_OUT_4") (pintype "passive+no_connect"))
    )
    (net (code "68") (name "unconnected-(U10-A5-Pad11)") (class "Default")
      (node (ref "U10") (pin "11") (pinfunction "A5_11") (pintype "passive+no_connect"))
    )
    (net (code "69") (name "unconnected-(U10-Y5-Pad10)") (class "Default")
      (node (ref "U10") (pin "10") (pinfunction "Y5_10") (pintype "passive+no_connect"))
    )
    (net (code "70") (name "unconnected-(USB1-ID-Pad4)") (class "Default")
      (node (ref "USB1") (pin "4") (pinfunction "ID_4") (pintype "passive+no_connect"))
    )
  )
)
